# MB1297_NFC_SAFE.net
KiCad netlist of a schematic drawn in Altium Designer
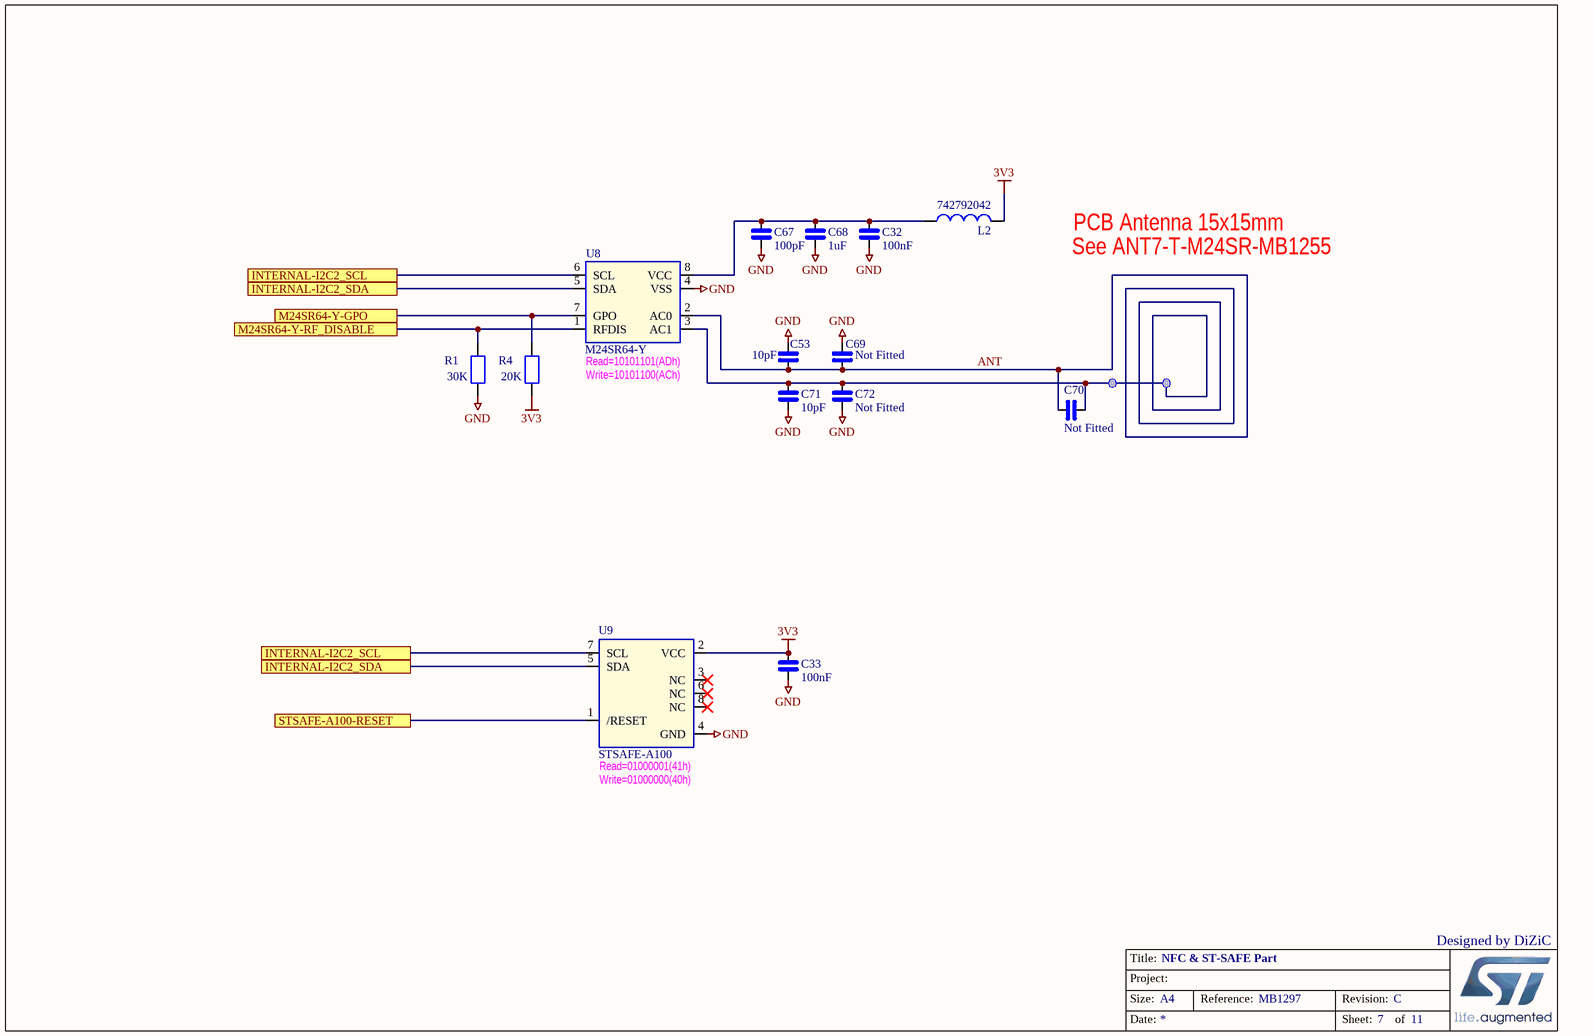
[diagram p0: MB1297_NFC_SAFE.SchDoc]

(export (version "E")
  (design (tool "Eeschema 10.0.6"))
  (components
    (comp (ref "C32")
      (value "100nF")
      (footprint "0402_CAP_NPOL")
      (description "Capacitor_not polarized")
      (libsource (lib "ST_Lib3D") (part "CAP_NPOL"))
    )
    (comp (ref "C33")
      (value "100nF")
      (footprint "0402_CAP_NPOL")
      (description "Capacitor_not polarized")
      (libsource (lib "ST_Lib3D") (part "CAP_NPOL"))
    )
    (comp (ref "C53")
      (value "10pF")
      (footprint "0402_CAP_NPOL")
      (description "Capacitor_not polarized")
      (libsource (lib "ST_Lib3D") (part "CAP_NPOL"))
    )
    (comp (ref "C67")
      (value "100pF")
      (footprint "0402_CAP_NPOL")
      (description "Capacitor_not polarized")
      (libsource (lib "ST_Lib3D") (part "CAP_NPOL"))
    )
    (comp (ref "C68")
      (value "1uF")
      (footprint "0402_CAP_NPOL")
      (description "Capacitor_not polarized")
      (libsource (lib "ST_Lib3D") (part "CAP_NPOL"))
    )
    (comp (ref "C69")
      (value "Not Fitted")
      (footprint "0402_CAP_NPOL")
      (description "Capacitor_not polarized")
      (libsource (lib "ST_Lib3D") (part "CAP_NPOL"))
    )
    (comp (ref "C70")
      (value "Not Fitted")
      (footprint "0402_CAP_NPOL")
      (description "Capacitor_not polarized")
      (libsource (lib "ST_Lib3D") (part "CAP_NPOL"))
    )
    (comp (ref "C71")
      (value "10pF")
      (footprint "0402_CAP_NPOL")
      (description "Capacitor_not polarized")
      (libsource (lib "ST_Lib3D") (part "CAP_NPOL"))
    )
    (comp (ref "C72")
      (value "Not Fitted")
      (footprint "0402_CAP_NPOL")
      (description "Capacitor_not polarized")
      (libsource (lib "ST_Lib3D") (part "CAP_NPOL"))
    )
    (comp (ref "L2")
      (value "742792042")
      (footprint "0603L")
      (description "Inductor")
      (fields (field (name "PUBLISHER") "Altium Limited"))
      (libsource (lib "Miscellaneous Devices") (part "Inductor"))
    )
    (comp (ref "R1")
      (value "30K")
      (footprint "0402_RES")
      (description "Resistor")
      (libsource (lib "ST_Lib3D") (part "RES"))
    )
    (comp (ref "R4")
      (value "20K")
      (footprint "0402_RES")
      (description "Resistor")
      (libsource (lib "ST_Lib3D") (part "RES"))
    )
    (comp (ref "U8")
      (value "M24SR64-Y")
      (footprint "SOP8")
      (description "M24SR64-Y  64K_EEPROM NFC/RFID")
      (libsource (lib "ST_Lib3D") (part "M24SR64-Y"))
    )
    (comp (ref "U9")
      (value "STSAFE-A100")
      (footprint "SOP8")
      (libsource (lib "ST_Lib3D") (part "STSAFE-A100"))
    )
  )
  (nets
    (net (code "1") (name "/ANT") (class "Default")
      (node (ref "C53") (pin "1") (pinfunction "1_1") (pintype "passive"))
      (node (ref "C69") (pin "1") (pinfunction "1_1") (pintype "passive"))
      (node (ref "C70") (pin "1") (pinfunction "1_1") (pintype "passive"))
      (node (ref "C70") (pin "2") (pinfunction "2_2") (pintype "passive"))
      (node (ref "C71") (pin "1") (pinfunction "1_1") (pintype "passive"))
      (node (ref "C72") (pin "1") (pinfunction "1_1") (pintype "passive"))
      (node (ref "U8") (pin "2") (pinfunction "AC0_2") (pintype "passive"))
      (node (ref "U8") (pin "3") (pinfunction "AC1_3") (pintype "passive"))
    )
    (net (code "2") (name "/INTERNAL-I2C2_SCL") (class "Default")
      (node (ref "U8") (pin "6") (pinfunction "SCL_6") (pintype "passive"))
      (node (ref "U9") (pin "7") (pinfunction "SCL_7") (pintype "passive"))
    )
    (net (code "3") (name "/INTERNAL-I2C2_SDA") (class "Default")
      (node (ref "U8") (pin "5") (pinfunction "SDA_5") (pintype "passive"))
      (node (ref "U9") (pin "5") (pinfunction "SDA_5") (pintype "passive"))
    )
    (net (code "4") (name "/M24SR64-Y-GPO") (class "Default")
      (node (ref "R4") (pin "2") (pinfunction "2_2") (pintype "passive"))
      (node (ref "U8") (pin "7") (pinfunction "GPO_7") (pintype "passive"))
    )
    (net (code "5") (name "/M24SR64-Y-RF_DISABLE") (class "Default")
      (node (ref "R1") (pin "2") (pinfunction "2_2") (pintype "passive"))
      (node (ref "U8") (pin "1") (pinfunction "RFDIS_1") (pintype "passive"))
    )
    (net (code "6") (name "/STSAFE-A100-RESET") (class "Default")
      (node (ref "U9") (pin "1") (pinfunction "/RESET_1") (pintype "passive"))
    )
    (net (code "7") (name "3V3") (class "Default")
      (node (ref "C33") (pin "1") (pinfunction "1_1") (pintype "passive"))
      (node (ref "L2") (pin "2") (pinfunction "2_2") (pintype "passive"))
      (node (ref "R4") (pin "1") (pinfunction "1_1") (pintype "passive"))
      (node (ref "U9") (pin "2") (pinfunction "VCC_2") (pintype "passive"))
    )
    (net (code "8") (name "GND") (class "Default")
      (node (ref "C32") (pin "2") (pinfunction "2_2") (pintype "passive"))
      (node (ref "C33") (pin "2") (pinfunction "2_2") (pintype "passive"))
      (node (ref "C53") (pin "2") (pinfunction "2_2") (pintype "passive"))
      (node (ref "C67") (pin "2") (pinfunction "2_2") (pintype "passive"))
      (node (ref "C68") (pin "2") (pinfunction "2_2") (pintype "passive"))
      (node (ref "C69") (pin "2") (pinfunction "2_2") (pintype "passive"))
      (node (ref "C71") (pin "2") (pinfunction "2_2") (pintype "passive"))
      (node (ref "C72") (pin "2") (pinfunction "2_2") (pintype "passive"))
      (node (ref "R1") (pin "1") (pinfunction "1_1") (pintype "passive"))
      (node (ref "U8") (pin "4") (pinfunction "VSS_4") (pintype "passive"))
      (node (ref "U9") (pin "4") (pinfunction "GND_4") (pintype "passive"))
    )
    (net (code "9") (name "Net-(U8-VCC)") (class "Default")
      (node (ref "C32") (pin "1") (pinfunction "1_1") (pintype "passive"))
      (node (ref "C67") (pin "1") (pinfunction "1_1") (pintype "passive"))
      (node (ref "C68") (pin "1") (pinfunction "1_1") (pintype "passive"))
      (node (ref "L2") (pin "1") (pinfunction "1_1") (pintype "passive"))
      (node (ref "U8") (pin "8") (pinfunction "VCC_8") (pintype "passive"))
    )
    (net (code "10") (name "unconnected-(U9-NC-Pad3)") (class "Default")
      (node (ref "U9") (pin "3") (pinfunction "NC_3") (pintype "passive+no_connect"))
    )
    (net (code "11") (name "unconnected-(U9-NC-Pad6)") (class "Default")
      (node (ref "U9") (pin "6") (pinfunction "NC_6") (pintype "passive+no_connect"))
    )
    (net (code "12") (name "unconnected-(U9-NC-Pad8)") (class "Default")
      (node (ref "U9") (pin "8") (pinfunction "NC_8") (pintype "passive+no_connect"))
    )
  )
)
